# 2_Input_Section.net
KiCad netlist of a schematic drawn in Altium Designer
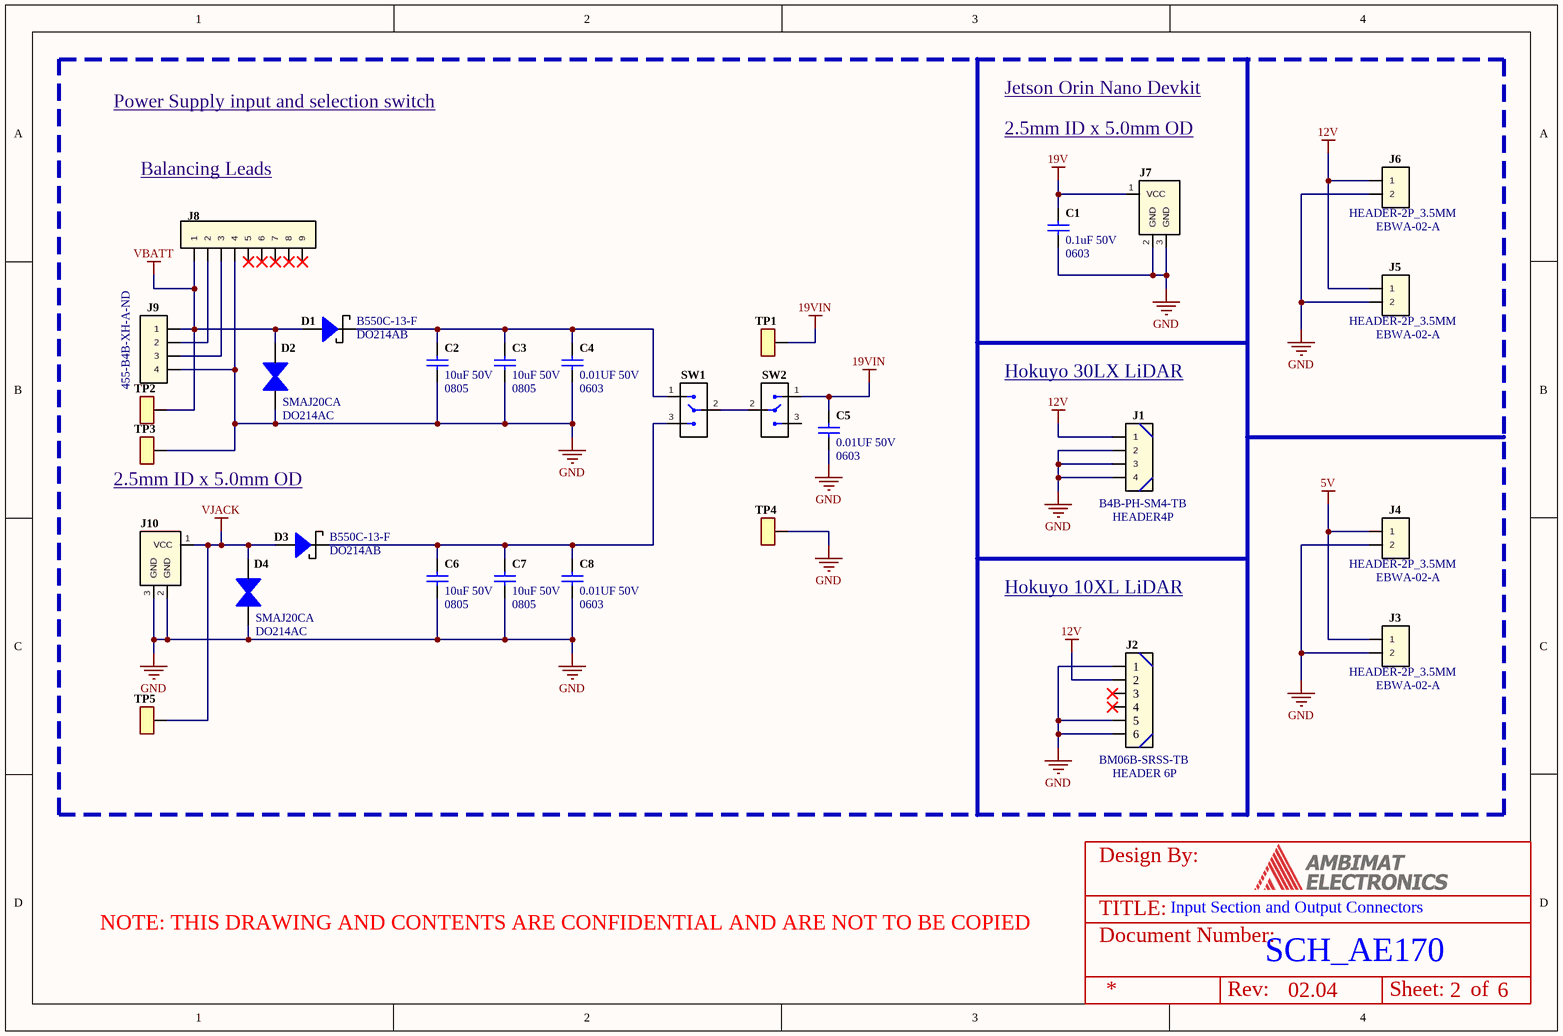
[diagram p0: 2. Input Section.SchDoc]

(export (version "E")
  (design (tool "Eeschema 10.0.6"))
  (components
    (comp (ref "C1")
      (value "CAP CER 0.1UF 50V X7R 0603")
      (footprint "LimLabDL:0603C")
      (fields
        (field (name "MANU PART NUMBER") "CC0603KRX7R9BB104")
        (field (name "MANUFACTURER") "Yageo")
        (field (name "VENDOR-1 PART NUMBER") "311-1344-1-ND")
        (field (name "PART NAME") "0.1uF 50V")
        (field (name "PCB FOOTPRINT") "0603")
      )
      (libsource (lib "LimLabDL") (part "CS0.1uF-50V0603"))
    )
    (comp (ref "C2")
      (value "CAP CER 10UF 50V X5R 0805")
      (footprint "LimLabDL:0805C")
      (fields
        (field (name "MANU PART NUMBER") "GRM21BR61H106KE43L")
        (field (name "MANUFACTURER") "Murata Electronics")
        (field (name "VENDOR-1 PART NUMBER") "490-18663-1-ND")
        (field (name "PART NAME") "10uF 50V")
        (field (name "PCB FOOTPRINT") "0805")
      )
      (libsource (lib "LimLabDL") (part "CS10uF-50V0805"))
    )
    (comp (ref "C3")
      (value "CAP CER 10UF 50V X5R 0805")
      (footprint "LimLabDL:0805C")
      (fields
        (field (name "MANU PART NUMBER") "GRM21BR61H106KE43L")
        (field (name "MANUFACTURER") "Murata Electronics")
        (field (name "VENDOR-1 PART NUMBER") "490-18663-1-ND")
        (field (name "PART NAME") "10uF 50V")
        (field (name "PCB FOOTPRINT") "0805")
      )
      (libsource (lib "LimLabDL") (part "CS10uF-50V0805"))
    )
    (comp (ref "C4")
      (value "CAP CER 10000PF 50V X7R 0603")
      (footprint "LimLabDL:0603C")
      (fields
        (field (name "MANU PART NUMBER") "CC0603KPX7R9BB103")
        (field (name "MANUFACTURER") "Yageo")
        (field (name "VENDOR-1 PART NUMBER") "311-1572-1-ND")
        (field (name "PART NAME") "0.01UF 50V")
        (field (name "PCB FOOTPRINT") "0603")
      )
      (libsource (lib "LimLabDL") (part "CS0.01uF-50V0603"))
    )
    (comp (ref "C5")
      (value "CAP CER 10000PF 50V X7R 0603")
      (footprint "LimLabDL:0603C")
      (fields
        (field (name "MANU PART NUMBER") "CC0603KPX7R9BB103")
        (field (name "MANUFACTURER") "Yageo")
        (field (name "VENDOR-1 PART NUMBER") "311-1572-1-ND")
        (field (name "PART NAME") "0.01UF 50V")
        (field (name "PCB FOOTPRINT") "0603")
      )
      (libsource (lib "LimLabDL") (part "CS0.01uF-50V0603"))
    )
    (comp (ref "C6")
      (value "CAP CER 10UF 50V X5R 0805")
      (footprint "LimLabDL:0805C")
      (fields
        (field (name "MANU PART NUMBER") "GRM21BR61H106KE43L")
        (field (name "MANUFACTURER") "Murata Electronics")
        (field (name "VENDOR-1 PART NUMBER") "490-18663-1-ND")
        (field (name "PART NAME") "10uF 50V")
        (field (name "PCB FOOTPRINT") "0805")
      )
      (libsource (lib "LimLabDL") (part "CS10uF-50V0805"))
    )
    (comp (ref "C7")
      (value "CAP CER 10UF 50V X5R 0805")
      (footprint "LimLabDL:0805C")
      (fields
        (field (name "MANU PART NUMBER") "GRM21BR61H106KE43L")
        (field (name "MANUFACTURER") "Murata Electronics")
        (field (name "VENDOR-1 PART NUMBER") "490-18663-1-ND")
        (field (name "PART NAME") "10uF 50V")
        (field (name "PCB FOOTPRINT") "0805")
      )
      (libsource (lib "LimLabDL") (part "CS10uF-50V0805"))
    )
    (comp (ref "C8")
      (value "CAP CER 10000PF 50V X7R 0603")
      (footprint "LimLabDL:0603C")
      (fields
        (field (name "MANU PART NUMBER") "CC0603KPX7R9BB103")
        (field (name "MANUFACTURER") "Yageo")
        (field (name "VENDOR-1 PART NUMBER") "311-1572-1-ND")
        (field (name "PART NAME") "0.01UF 50V")
        (field (name "PCB FOOTPRINT") "0603")
      )
      (libsource (lib "LimLabDL") (part "CS0.01uF-50V0603"))
    )
    (comp (ref "D1")
      (value "DIODE SCHOTTKY 50V 5A SMC")
      (footprint "LimLabDL:DO-214AB-SHKY")
      (fields
        (field (name "MANU PART NUMBER") "B550C-13-F")
        (field (name "MANUFACTURER") "Diodes Incorporated")
        (field (name "VENDOR-1 PART NUMBER") "B550C-FDICT-ND")
        (field (name "PCB FOOTPRINT") "DO214AB")
        (field (name "PART NAME") "B550C-13-F")
      )
      (libsource (lib "LimLabDL") (part "DS-B550C-13-F"))
    )
    (comp (ref "D2")
      (value "TVS DIODE 20VWM 32.4VC DO214AC")
      (footprint "LimLabDL:DO-214AC")
      (fields
        (field (name "MANU PART NUMBER") "SMAJ20CA")
        (field (name "MANUFACTURER") "Littelfuse Inc.")
        (field (name "VENDOR-1 PART NUMBER") "SMAJ20CALFCT-ND")
        (field (name "PCB FOOTPRINT") "DO214AC")
        (field (name "PART NAME") "SMAJ20CA")
      )
      (libsource (lib "LimLabDL") (part "DS-SMAJ20CA"))
    )
    (comp (ref "D3")
      (value "DIODE SCHOTTKY 50V 5A SMC")
      (footprint "LimLabDL:DO-214AB-SHKY")
      (fields
        (field (name "MANU PART NUMBER") "B550C-13-F")
        (field (name "MANUFACTURER") "Diodes Incorporated")
        (field (name "VENDOR-1 PART NUMBER") "B550C-FDICT-ND")
        (field (name "PCB FOOTPRINT") "DO214AB")
        (field (name "PART NAME") "B550C-13-F")
      )
      (libsource (lib "LimLabDL") (part "DS-B550C-13-F"))
    )
    (comp (ref "D4")
      (value "TVS DIODE 20VWM 32.4VC DO214AC")
      (footprint "LimLabDL:DO-214AC")
      (fields
        (field (name "MANU PART NUMBER") "SMAJ20CA")
        (field (name "MANUFACTURER") "Littelfuse Inc.")
        (field (name "VENDOR-1 PART NUMBER") "SMAJ20CALFCT-ND")
        (field (name "PCB FOOTPRINT") "DO214AC")
        (field (name "PART NAME") "SMAJ20CA")
      )
      (libsource (lib "LimLabDL") (part "DS-SMAJ20CA"))
    )
    (comp (ref "J1")
      (value "CONN HEADER SMD 4POS 2MM")
      (footprint "LimLabDL:JST_B4B-PH-SM4-TB")
      (fields
        (field (name "MANU PART NUMBER") "B4B-PH-SM4-TB")
        (field (name "MANUFACTURER") "JST Sales America Inc.")
        (field (name "PART NAME") "HEADER4P")
        (field (name "VENDOR-1 PART NUMBER") "455-B4B-PH-SM4-TBCT-ND")
      )
      (libsource (lib "LimLabDL") (part "CON2.0P-4x1SMT"))
    )
    (comp (ref "J2")
      (value "CONN HEADER SMD 6POS 1MM")
      (footprint "LimLabDL:BM06B-SRSS-TB_JST")
      (fields
        (field (name "MANUFACTURER") "JST Sales America Inc.")
        (field (name "VENDOR-1 PART NUMBER") "455-BM06B-SRSS-TBCT-ND")
        (field (name "MANU PART NUMBER") "BM06B-SRSS-TB")
        (field (name "PCB FOOTPRINT") "HEADER 6P")
      )
      (libsource (lib "LimLabDL") (part "CON1.0P-6x1 SMT"))
    )
    (comp (ref "J3")
      (value "EURO BLOCK 2P")
      (footprint "LimLabDL:Header3.5")
      (fields
        (field (name "MANU PART NUMBER") "EBWA-02-A")
        (field (name "MANUFACTURER") "Adam Tech")
        (field (name "PCB FOOTPRINT") "HEADER-2P_3.5MM")
        (field (name "VENDOR-1 PART NUMBER") "2057-EBWA-02-A-ND")
      )
      (libsource (lib "LimLabDL") (part "CON3.5P-2x1TH_STRT"))
    )
    (comp (ref "J4")
      (value "EURO BLOCK 2P")
      (footprint "LimLabDL:Header3.5")
      (fields
        (field (name "MANU PART NUMBER") "EBWA-02-A")
        (field (name "MANUFACTURER") "Adam Tech")
        (field (name "PCB FOOTPRINT") "HEADER-2P_3.5MM")
        (field (name "VENDOR-1 PART NUMBER") "2057-EBWA-02-A-ND")
      )
      (libsource (lib "LimLabDL") (part "CON3.5P-2x1TH_STRT"))
    )
    (comp (ref "J5")
      (value "EURO BLOCK 2P")
      (footprint "LimLabDL:Header3.5")
      (fields
        (field (name "MANU PART NUMBER") "EBWA-02-A")
        (field (name "MANUFACTURER") "Adam Tech")
        (field (name "PCB FOOTPRINT") "HEADER-2P_3.5MM")
        (field (name "VENDOR-1 PART NUMBER") "2057-EBWA-02-A-ND")
      )
      (libsource (lib "LimLabDL") (part "CON3.5P-2x1TH_STRT"))
    )
    (comp (ref "J6")
      (value "EURO BLOCK 2P")
      (footprint "LimLabDL:Header3.5")
      (fields
        (field (name "MANU PART NUMBER") "EBWA-02-A")
        (field (name "MANUFACTURER") "Adam Tech")
        (field (name "PCB FOOTPRINT") "HEADER-2P_3.5MM")
        (field (name "VENDOR-1 PART NUMBER") "2057-EBWA-02-A-ND")
      )
      (libsource (lib "LimLabDL") (part "CON3.5P-2x1TH_STRT"))
    )
    (comp (ref "J7")
      (value "CONN PWR JACK 2.5X5.5MM SOLDER")
      (footprint "LimLabDL:PJ-050BH")
      (fields
        (field (name "MANU PART NUMBER") "PJ-050BH")
        (field (name "MANUFACTURER") "CUI Inc")
        (field (name "VENDOR-1 PART NUMBER") "CP-050BH-ND")
      )
      (libsource (lib "LimLabDL") (part "CON3P-PJ-050BH"))
    )
    (comp (ref "J8")
      (value "HEADER 1x9")
      (footprint "LimLabDL:HEADER-9P_2.54MM")
      (description "CONN HEADER 9PS 2.54MM")
      (libsource (lib "LimLabDL") (part "CON2.54P-1x9"))
    )
    (comp (ref "J9")
      (value "CONN HEADER VERT 4POS 2.5MM")
      (footprint "LimLabDL:JST_B4B-XH-A")
      (fields
        (field (name "MANU PART NUMBER") "B4B-XH-A")
        (field (name "MANUFACTURER") "JST Sales America Inc.")
        (field (name "VENDOR-1 PART NUMBER") "455-B4B-XH-A-ND")
      )
      (libsource (lib "LimLabDL") (part "CON2.5P-4x1TH"))
    )
    (comp (ref "J10")
      (value "CONN PWR JACK 2.5X5.5MM SOLDER")
      (footprint "LimLabDL:PJ-050BH")
      (fields
        (field (name "MANU PART NUMBER") "PJ-050BH")
        (field (name "MANUFACTURER") "CUI Inc")
        (field (name "VENDOR-1 PART NUMBER") "CP-050BH-ND")
      )
      (libsource (lib "") (part "CON3P-PJ-050BH_1"))
    )
    (comp (ref "SW1")
      (value "SWITCH TOGGLE SPDT 7.5A 125V")
      (footprint "LimLabDL:E101SYZQE")
      (fields
        (field (name "MANU PART NUMBER") "E101SYZQE")
        (field (name "MANUFACTURER") "C&K")
        (field (name "VENDOR-1 PART NUMBER") "CKN1519-ND")
      )
      (libsource (lib "LimLabDL") (part "SW-E101SYZQE"))
    )
    (comp (ref "SW2")
      (value "SWITCH TOGGLE SPDT 7.5A 125V")
      (footprint "LimLabDL:E101SYZQE")
      (fields
        (field (name "MANU PART NUMBER") "E101SYZQE")
        (field (name "MANUFACTURER") "C&K")
        (field (name "VENDOR-1 PART NUMBER") "CKN1519-ND")
      )
      (libsource (lib "LimLabDL") (part "SW-E101SYZQE"))
    )
    (comp (ref "TP1")
      (value "TEST POINT")
      (footprint "LimLabDL:TP-1.5mmSMD")
      (description "SMD TEST POINT")
      (libsource (lib "LimLabDL") (part "TP-1.5mmSMD"))
    )
    (comp (ref "TP2")
      (value "TEST POINT")
      (footprint "LimLabDL:TP-1.5mmSMD")
      (description "SMD TEST POINT")
      (libsource (lib "LimLabDL") (part "TP-1.5mmSMD"))
    )
    (comp (ref "TP3")
      (value "TEST POINT")
      (footprint "LimLabDL:TP-1.5mmSMD")
      (description "SMD TEST POINT")
      (libsource (lib "LimLabDL") (part "TP-1.5mmSMD"))
    )
    (comp (ref "TP4")
      (value "TEST POINT")
      (footprint "LimLabDL:TP-1.5mmSMD")
      (description "SMD TEST POINT")
      (libsource (lib "LimLabDL") (part "TP-1.5mmSMD"))
    )
    (comp (ref "TP5")
      (value "TEST POINT")
      (footprint "LimLabDL:TP-1.5mmSMD")
      (description "SMD TEST POINT")
      (libsource (lib "LimLabDL") (part "TP-1.5mmSMD"))
    )
  )
  (nets
    (net (code "1") (name "5V") (class "Default")
      (node (ref "J3") (pin "1") (pinfunction "1_1") (pintype "passive"))
      (node (ref "J4") (pin "1") (pinfunction "1_1") (pintype "passive"))
    )
    (net (code "2") (name "12V") (class "Default")
      (node (ref "J1") (pin "1") (pinfunction "1_1") (pintype "passive"))
      (node (ref "J2") (pin "2") (pinfunction "2_2") (pintype "passive"))
      (node (ref "J5") (pin "1") (pinfunction "1_1") (pintype "passive"))
      (node (ref "J6") (pin "1") (pinfunction "1_1") (pintype "passive"))
    )
    (net (code "3") (name "19V") (class "Default")
      (node (ref "C1") (pin "2") (pinfunction "2_2") (pintype "passive"))
      (node (ref "J7") (pin "1") (pinfunction "VCC_1") (pintype "passive"))
    )
    (net (code "4") (name "19VIN") (class "Default")
      (node (ref "C5") (pin "1") (pinfunction "1_1") (pintype "passive"))
      (node (ref "SW2") (pin "1") (pinfunction "1_1") (pintype "passive"))
      (node (ref "TP1") (pin "1") (pinfunction "1_1") (pintype "passive"))
    )
    (net (code "5") (name "GND") (class "Default")
      (node (ref "C1") (pin "1") (pinfunction "1_1") (pintype "passive"))
      (node (ref "C2") (pin "2") (pinfunction "2_2") (pintype "passive"))
      (node (ref "C3") (pin "2") (pinfunction "2_2") (pintype "passive"))
      (node (ref "C4") (pin "2") (pinfunction "2_2") (pintype "passive"))
      (node (ref "C5") (pin "2") (pinfunction "2_2") (pintype "passive"))
      (node (ref "C6") (pin "2") (pinfunction "2_2") (pintype "passive"))
      (node (ref "C7") (pin "2") (pinfunction "2_2") (pintype "passive"))
      (node (ref "C8") (pin "2") (pinfunction "2_2") (pintype "passive"))
      (node (ref "D2") (pin "1") (pinfunction "A_1") (pintype "passive"))
      (node (ref "D4") (pin "1") (pinfunction "A_1") (pintype "passive"))
      (node (ref "J1") (pin "2") (pinfunction "2_2") (pintype "passive"))
      (node (ref "J1") (pin "3") (pinfunction "3_3") (pintype "passive"))
      (node (ref "J1") (pin "4") (pinfunction "4_4") (pintype "passive"))
      (node (ref "J10") (pin "2") (pinfunction "GND_2") (pintype "passive"))
      (node (ref "J10") (pin "3") (pinfunction "GND_3") (pintype "passive"))
      (node (ref "J2") (pin "1") (pinfunction "1_1") (pintype "passive"))
      (node (ref "J2") (pin "5") (pinfunction "5_5") (pintype "passive"))
      (node (ref "J2") (pin "6") (pinfunction "6_6") (pintype "passive"))
      (node (ref "J3") (pin "2") (pinfunction "2_2") (pintype "passive"))
      (node (ref "J4") (pin "2") (pinfunction "2_2") (pintype "passive"))
      (node (ref "J5") (pin "2") (pinfunction "2_2") (pintype "passive"))
      (node (ref "J6") (pin "2") (pinfunction "2_2") (pintype "passive"))
      (node (ref "J7") (pin "2") (pinfunction "GND_2") (pintype "passive"))
      (node (ref "J7") (pin "3") (pinfunction "GND_3") (pintype "passive"))
      (node (ref "J8") (pin "4") (pinfunction "4_4") (pintype "passive"))
      (node (ref "J9") (pin "4") (pinfunction "4_4") (pintype "passive"))
      (node (ref "TP3") (pin "1") (pinfunction "1_1") (pintype "passive"))
      (node (ref "TP4") (pin "1") (pinfunction "1_1") (pintype "passive"))
    )
    (net (code "6") (name "Net-(C2-Pad1)") (class "Default")
      (node (ref "C2") (pin "1") (pinfunction "1_1") (pintype "passive"))
      (node (ref "C3") (pin "1") (pinfunction "1_1") (pintype "passive"))
      (node (ref "C4") (pin "1") (pinfunction "1_1") (pintype "passive"))
      (node (ref "D1") (pin "1") (pinfunction "1_1") (pintype "passive"))
      (node (ref "SW1") (pin "1") (pinfunction "1_1") (pintype "passive"))
    )
    (net (code "7") (name "Net-(C6-Pad1)") (class "Default")
      (node (ref "C6") (pin "1") (pinfunction "1_1") (pintype "passive"))
      (node (ref "C7") (pin "1") (pinfunction "1_1") (pintype "passive"))
      (node (ref "C8") (pin "1") (pinfunction "1_1") (pintype "passive"))
      (node (ref "D3") (pin "1") (pinfunction "1_1") (pintype "passive"))
      (node (ref "SW1") (pin "3") (pinfunction "3_3") (pintype "passive"))
    )
    (net (code "8") (name "Net-(J8-Pad2)") (class "Default")
      (node (ref "J8") (pin "2") (pinfunction "2_2") (pintype "passive"))
      (node (ref "J9") (pin "2") (pinfunction "2_2") (pintype "passive"))
    )
    (net (code "9") (name "Net-(J8-Pad3)") (class "Default")
      (node (ref "J8") (pin "3") (pinfunction "3_3") (pintype "passive"))
      (node (ref "J9") (pin "3") (pinfunction "3_3") (pintype "passive"))
    )
    (net (code "10") (name "Net-(SW1-Pad2)") (class "Default")
      (node (ref "SW1") (pin "2") (pinfunction "2_2") (pintype "passive"))
      (node (ref "SW2") (pin "2") (pinfunction "2_2") (pintype "passive"))
    )
    (net (code "11") (name "VBATT") (class "Default")
      (node (ref "D1") (pin "2") (pinfunction "2_2") (pintype "passive"))
      (node (ref "D2") (pin "2") (pinfunction "K_2") (pintype "passive"))
      (node (ref "J8") (pin "1") (pinfunction "1_1") (pintype "passive"))
      (node (ref "J9") (pin "1") (pinfunction "1_1") (pintype "passive"))
      (node (ref "TP2") (pin "1") (pinfunction "1_1") (pintype "passive"))
    )
    (net (code "12") (name "VJACK") (class "Default")
      (node (ref "D3") (pin "2") (pinfunction "2_2") (pintype "passive"))
      (node (ref "D4") (pin "2") (pinfunction "K_2") (pintype "passive"))
      (node (ref "J10") (pin "1") (pinfunction "VCC_1") (pintype "passive"))
      (node (ref "TP5") (pin "1") (pinfunction "1_1") (pintype "passive"))
    )
    (net (code "13") (name "unconnected-(J2-Pad3)") (class "Default")
      (node (ref "J2") (pin "3") (pinfunction "3_3") (pintype "passive+no_connect"))
    )
    (net (code "14") (name "unconnected-(J2-Pad4)") (class "Default")
      (node (ref "J2") (pin "4") (pinfunction "4_4") (pintype "passive+no_connect"))
    )
    (net (code "15") (name "unconnected-(J8-Pad5)") (class "Default")
      (node (ref "J8") (pin "5") (pinfunction "5_5") (pintype "passive+no_connect"))
    )
    (net (code "16") (name "unconnected-(J8-Pad6)") (class "Default")
      (node (ref "J8") (pin "6") (pinfunction "6_6") (pintype "passive+no_connect"))
    )
    (net (code "17") (name "unconnected-(J8-Pad7)") (class "Default")
      (node (ref "J8") (pin "7") (pinfunction "7_7") (pintype "passive+no_connect"))
    )
    (net (code "18") (name "unconnected-(J8-Pad8)") (class "Default")
      (node (ref "J8") (pin "8") (pinfunction "8_8") (pintype "passive+no_connect"))
    )
    (net (code "19") (name "unconnected-(J8-Pad9)") (class "Default")
      (node (ref "J8") (pin "9") (pinfunction "9_9") (pintype "passive+no_connect"))
    )
    (net (code "20") (name "unconnected-(SW2-Pad3)") (class "Default")
      (node (ref "SW2") (pin "3") (pinfunction "3_3") (pintype "passive"))
    )
  )
)
